# LMDoorAlarm.net
KiCad netlist of a schematic drawn in EAGLE
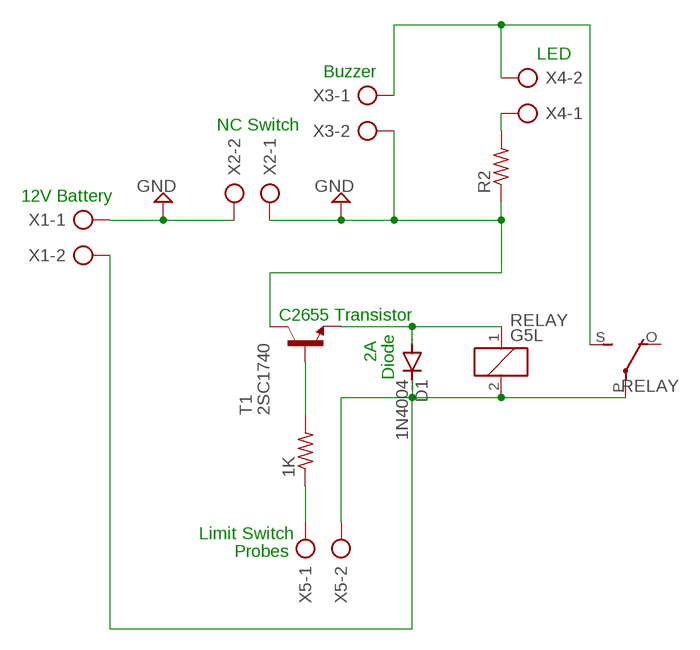
[diagram p0: schematic, sheet 1]

(export (version "E")
  (design (tool "Eeschema 10.0.6"))
  (components
    (comp (ref "1K")
      (value "R-US_0207/10")
      (footprint "eagle-import:0207_10")
      (libsource (lib "eagle-import") (part "R-US_0207/10"))
    )
    (comp (ref "D1")
      (value "1N4004")
      (footprint "eagle-import:DO41-10")
      (libsource (lib "eagle-import") (part "1N4004"))
    )
    (comp (ref "R2")
      (value "R-US_0207/10")
      (footprint "eagle-import:0207_10")
      (libsource (lib "eagle-import") (part "R-US_0207/10"))
    )
    (comp (ref "RELAY")
      (value "G5L")
      (footprint "eagle-import:G5LE")
      (libsource (lib "eagle-import") (part "G5L"))
    )
    (comp (ref "T1")
      (value "2SC1740")
      (footprint "eagle-import:TO92-ECB")
      (libsource (lib "eagle-import") (part "2SC1740"))
    )
    (comp (ref "X1")
      (value "AK500/2")
      (footprint "eagle-import:AK500_2")
      (libsource (lib "eagle-import") (part "AK500/2"))
    )
    (comp (ref "X2")
      (value "AK500/2")
      (footprint "eagle-import:AK500_2")
      (libsource (lib "eagle-import") (part "AK500/2"))
    )
    (comp (ref "X3")
      (value "AK500/2")
      (footprint "eagle-import:AK500_2")
      (libsource (lib "eagle-import") (part "AK500/2"))
    )
    (comp (ref "X4")
      (value "AK500/2")
      (footprint "eagle-import:AK500_2")
      (libsource (lib "eagle-import") (part "AK500/2"))
    )
    (comp (ref "X5")
      (value "AK500/2")
      (footprint "eagle-import:AK500_2")
      (libsource (lib "eagle-import") (part "AK500/2"))
    )
  )
  (nets
    (net (code "1") (name "GND") (class "Default")
      (node (ref "R2") (pin "1") (pinfunction "1_1") (pintype "passive"))
      (node (ref "T1") (pin "C") (pinfunction "C_C") (pintype "passive"))
      (node (ref "X1") (pin "1") (pinfunction "KL_1") (pintype "passive"))
      (node (ref "X2") (pin "1") (pinfunction "KL_1") (pintype "passive"))
      (node (ref "X2") (pin "2") (pinfunction "KL_2") (pintype "passive"))
      (node (ref "X3") (pin "2") (pinfunction "KL_2") (pintype "passive"))
    )
    (net (code "2") (name "Net-(1K-Pad2)") (class "Default")
      (node (ref "1K") (pin "2") (pinfunction "2_2") (pintype "passive"))
      (node (ref "T1") (pin "B") (pinfunction "B_B") (pintype "passive"))
    )
    (net (code "3") (name "Net-(D1-PadA)") (class "Default")
      (node (ref "D1") (pin "A") (pinfunction "A_A") (pintype "passive"))
      (node (ref "RELAY") (pin "1") (pinfunction "1_1") (pintype "passive"))
      (node (ref "T1") (pin "E") (pinfunction "E_E") (pintype "passive"))
    )
    (net (code "4") (name "Net-(X1B-KL)") (class "Default")
      (node (ref "D1") (pin "C") (pinfunction "C_C") (pintype "passive"))
      (node (ref "RELAY") (pin "2") (pinfunction "2_2") (pintype "passive"))
      (node (ref "RELAY") (pin "P") (pinfunction "P_P") (pintype "passive"))
      (node (ref "X1") (pin "2") (pinfunction "KL_2") (pintype "passive"))
      (node (ref "X5") (pin "2") (pinfunction "KL_2") (pintype "passive"))
    )
    (net (code "5") (name "Net-(X3A-KL)") (class "Default")
      (node (ref "RELAY") (pin "S") (pinfunction "S_S") (pintype "passive"))
      (node (ref "X3") (pin "1") (pinfunction "KL_1") (pintype "passive"))
      (node (ref "X4") (pin "2") (pinfunction "KL_2") (pintype "passive"))
    )
    (net (code "6") (name "Net-(X4A-KL)") (class "Default")
      (node (ref "R2") (pin "2") (pinfunction "2_2") (pintype "passive"))
      (node (ref "X4") (pin "1") (pinfunction "KL_1") (pintype "passive"))
    )
    (net (code "7") (name "Net-(X5A-KL)") (class "Default")
      (node (ref "1K") (pin "1") (pinfunction "1_1") (pintype "passive"))
      (node (ref "X5") (pin "1") (pinfunction "KL_1") (pintype "passive"))
    )
    (net (code "8") (name "unconnected-(RELAY-PadO)") (class "Default")
      (node (ref "RELAY") (pin "O") (pinfunction "O_O") (pintype "passive"))
    )
  )
)
